# Main.net
KiCad netlist of a schematic drawn in Altium Designer
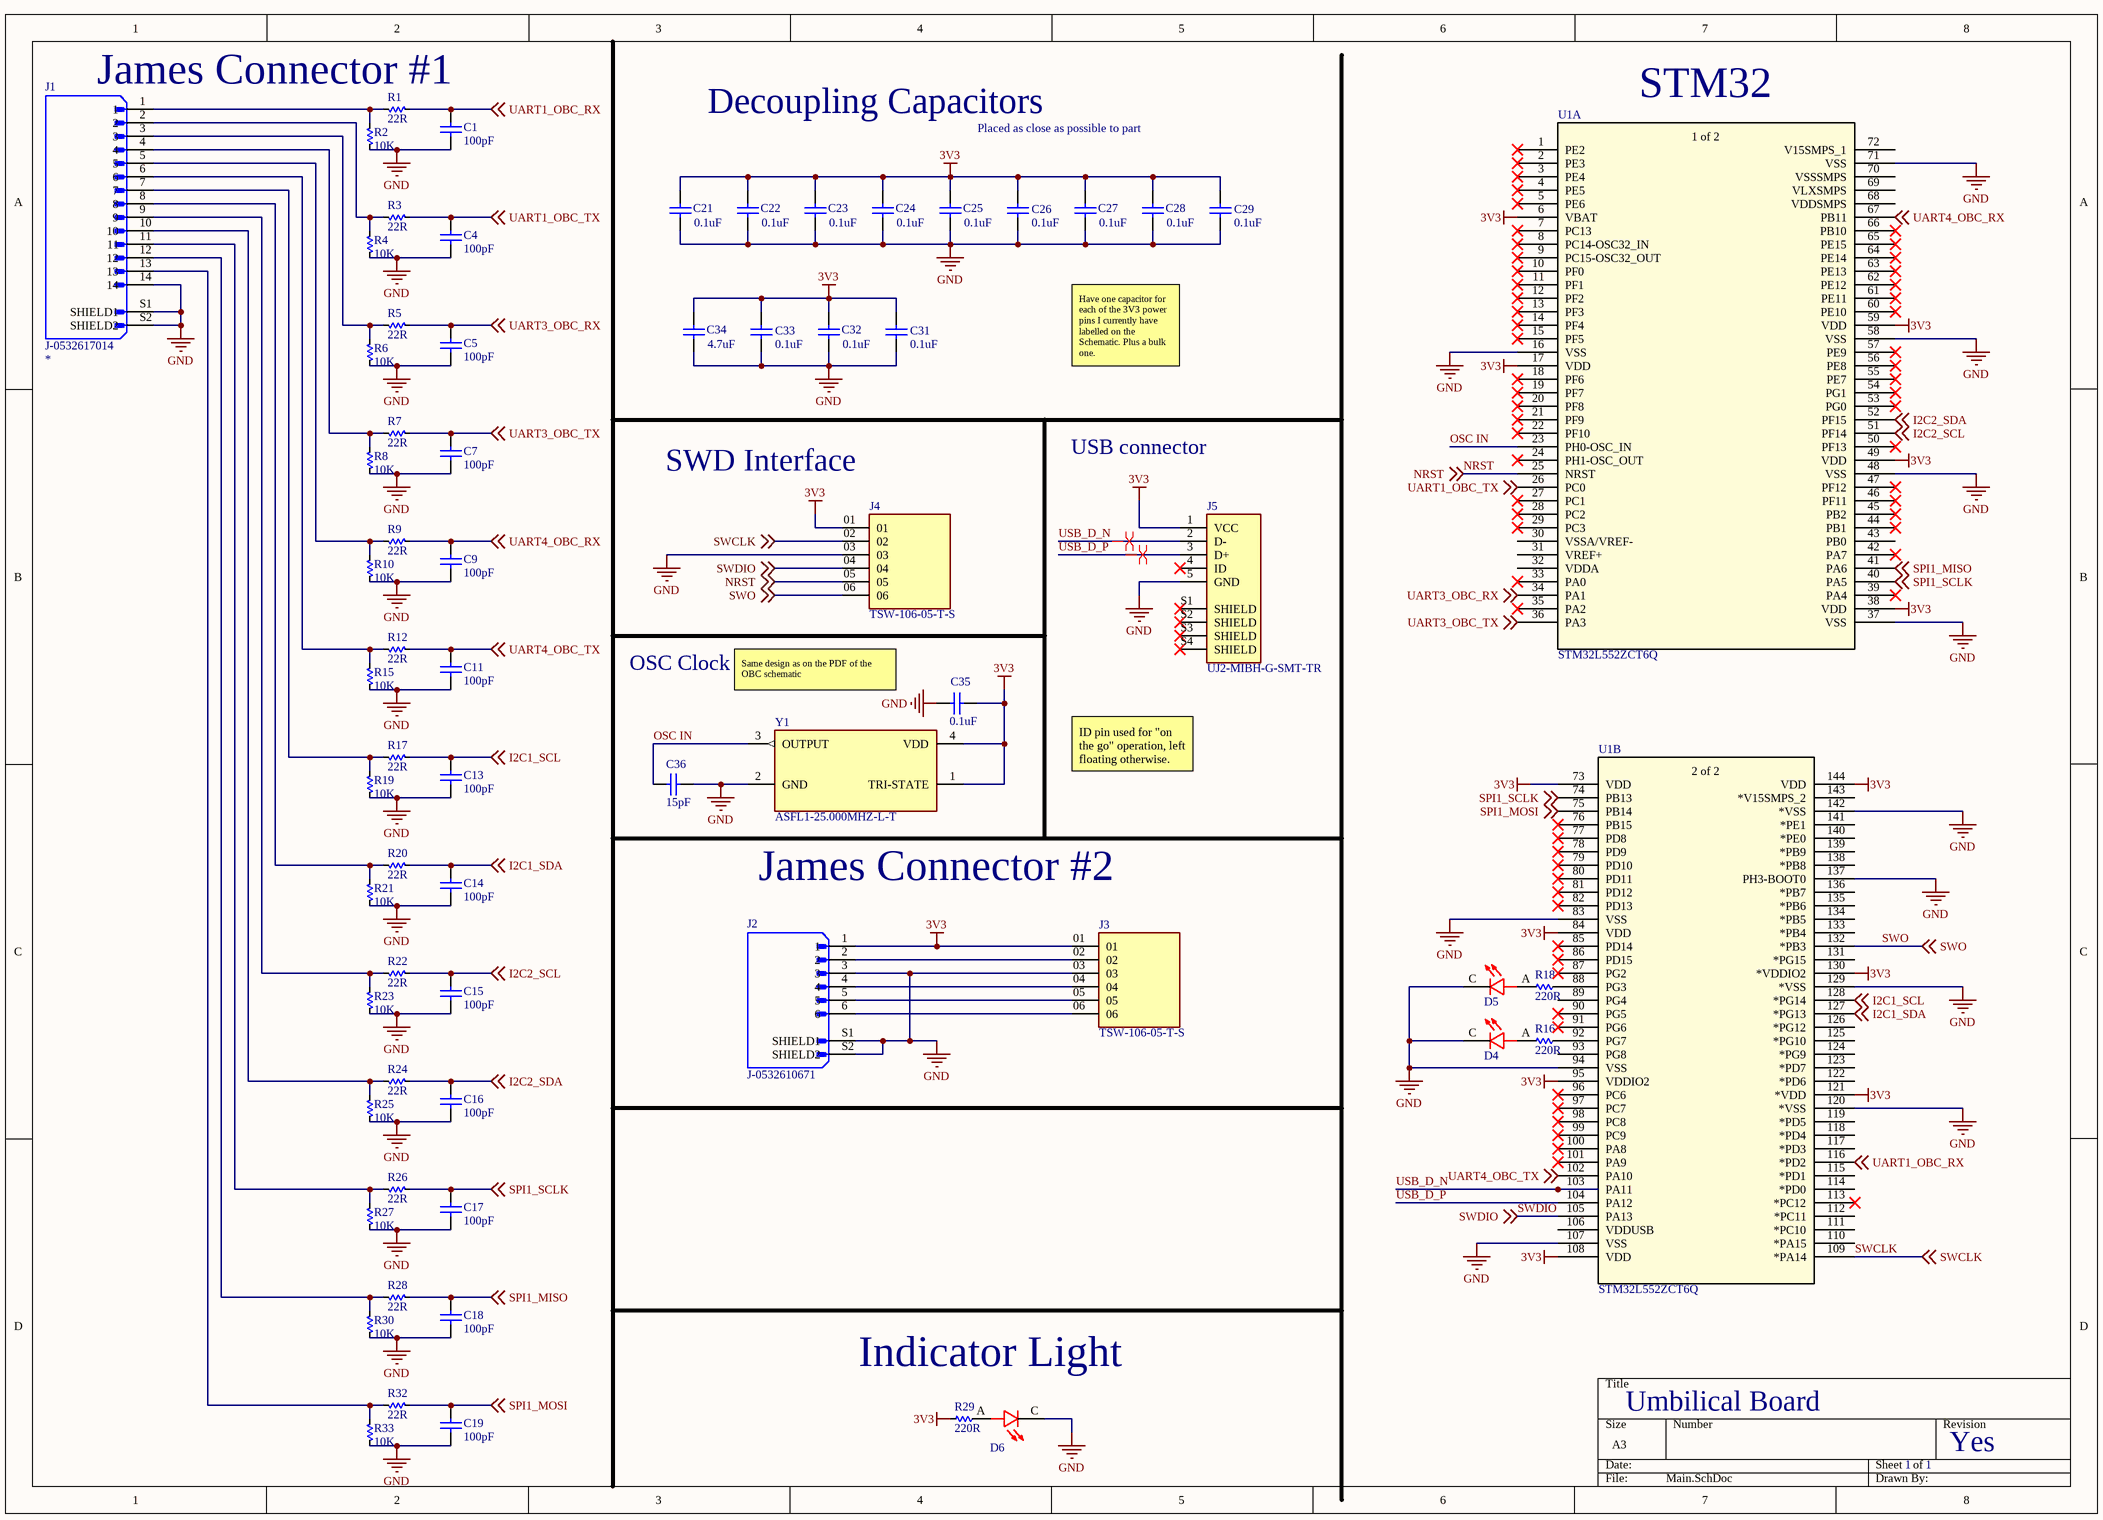
[diagram p0: Main.SchDoc]

(export (version "E")
  (design (tool "Eeschema 10.0.6"))
  (components
    (comp (ref "C1")
      (value "100pF")
      (footprint "CAPC1608X95X40NL15T15")
      (fields (field (name "PART NUMBER") "VJ0603A101FXACW1BC") (field (name "MANUFACTURER") "Vitramon"))
      (libsource (lib "Altium Content Vault") (part "CAP"))
    )
    (comp (ref "C4")
      (value "100pF")
      (footprint "CAPC1608X95X40NL15T15")
      (fields (field (name "PART NUMBER") "VJ0603A101FXACW1BC") (field (name "MANUFACTURER") "Vitramon"))
      (libsource (lib "Altium Content Vault") (part "CAP"))
    )
    (comp (ref "C5")
      (value "100pF")
      (footprint "CAPC1608X95X40NL15T15")
      (fields (field (name "PART NUMBER") "VJ0603A101FXACW1BC") (field (name "MANUFACTURER") "Vitramon"))
      (libsource (lib "Altium Content Vault") (part "CAP"))
    )
    (comp (ref "C7")
      (value "100pF")
      (footprint "CAPC1608X95X40NL15T15")
      (fields (field (name "PART NUMBER") "VJ0603A101FXACW1BC") (field (name "MANUFACTURER") "Vitramon"))
      (libsource (lib "Altium Content Vault") (part "CAP"))
    )
    (comp (ref "C9")
      (value "100pF")
      (footprint "CAPC1608X95X40NL15T15")
      (fields (field (name "PART NUMBER") "VJ0603A101FXACW1BC") (field (name "MANUFACTURER") "Vitramon"))
      (libsource (lib "Altium Content Vault") (part "CAP"))
    )
    (comp (ref "C11")
      (value "100pF")
      (footprint "CAPC1608X95X40NL15T15")
      (fields (field (name "PART NUMBER") "VJ0603A101FXACW1BC") (field (name "MANUFACTURER") "Vitramon"))
      (libsource (lib "Altium Content Vault") (part "CAP"))
    )
    (comp (ref "C13")
      (value "100pF")
      (footprint "CAPC1608X95X40NL15T15")
      (fields (field (name "PART NUMBER") "VJ0603A101FXACW1BC") (field (name "MANUFACTURER") "Vitramon"))
      (libsource (lib "Altium Content Vault") (part "CAP"))
    )
    (comp (ref "C14")
      (value "100pF")
      (footprint "CAPC1608X95X40NL15T15")
      (fields (field (name "PART NUMBER") "VJ0603A101FXACW1BC") (field (name "MANUFACTURER") "Vitramon"))
      (libsource (lib "Altium Content Vault") (part "CAP"))
    )
    (comp (ref "C15")
      (value "100pF")
      (footprint "CAPC1608X95X40NL15T15")
      (fields (field (name "PART NUMBER") "VJ0603A101FXACW1BC") (field (name "MANUFACTURER") "Vitramon"))
      (libsource (lib "Altium Content Vault") (part "CAP"))
    )
    (comp (ref "C16")
      (value "100pF")
      (footprint "CAPC1608X95X40NL15T15")
      (fields (field (name "PART NUMBER") "VJ0603A101FXACW1BC") (field (name "MANUFACTURER") "Vitramon"))
      (libsource (lib "Altium Content Vault") (part "CAP"))
    )
    (comp (ref "C17")
      (value "100pF")
      (footprint "CAPC1608X95X40NL15T15")
      (fields (field (name "PART NUMBER") "VJ0603A101FXACW1BC") (field (name "MANUFACTURER") "Vitramon"))
      (libsource (lib "Altium Content Vault") (part "CAP"))
    )
    (comp (ref "C18")
      (value "100pF")
      (footprint "CAPC1608X95X40NL15T15")
      (fields (field (name "PART NUMBER") "VJ0603A101FXACW1BC") (field (name "MANUFACTURER") "Vitramon"))
      (libsource (lib "Altium Content Vault") (part "CAP"))
    )
    (comp (ref "C19")
      (value "100pF")
      (footprint "CAPC1608X95X40NL15T15")
      (fields (field (name "PART NUMBER") "VJ0603A101FXACW1BC") (field (name "MANUFACTURER") "Vitramon"))
      (libsource (lib "Altium Content Vault") (part "CAP"))
    )
    (comp (ref "C21")
      (value "0.1uF")
      (footprint "CAPC1608X95X40NL15T15")
      (fields (field (name "PART NUMBER") "VJ0603A101FXACW1BC") (field (name "MANUFACTURER") "Vitramon"))
      (libsource (lib "Altium Content Vault") (part "CAP"))
    )
    (comp (ref "C22")
      (value "0.1uF")
      (footprint "CAPC1608X95X40NL15T15")
      (fields (field (name "PART NUMBER") "VJ0603A101FXACW1BC") (field (name "MANUFACTURER") "Vitramon"))
      (libsource (lib "Altium Content Vault") (part "CAP"))
    )
    (comp (ref "C23")
      (value "0.1uF")
      (footprint "CAPC1608X95X40NL15T15")
      (fields (field (name "PART NUMBER") "VJ0603A101FXACW1BC") (field (name "MANUFACTURER") "Vitramon"))
      (libsource (lib "Altium Content Vault") (part "CAP"))
    )
    (comp (ref "C24")
      (value "0.1uF")
      (footprint "CAPC1608X95X40NL15T15")
      (fields (field (name "PART NUMBER") "VJ0603A101FXACW1BC") (field (name "MANUFACTURER") "Vitramon"))
      (libsource (lib "Altium Content Vault") (part "CAP"))
    )
    (comp (ref "C25")
      (value "0.1uF")
      (footprint "CAPC1608X95X40NL15T15")
      (fields (field (name "PART NUMBER") "VJ0603A101FXACW1BC") (field (name "MANUFACTURER") "Vitramon"))
      (libsource (lib "Altium Content Vault") (part "CAP"))
    )
    (comp (ref "C26")
      (value "0.1uF")
      (footprint "CAPC1608X95X40NL15T15")
      (fields (field (name "PART NUMBER") "VJ0603A101FXACW1BC") (field (name "MANUFACTURER") "Vitramon"))
      (libsource (lib "Altium Content Vault") (part "CAP"))
    )
    (comp (ref "C27")
      (value "0.1uF")
      (footprint "CAPC1608X95X40NL15T15")
      (fields (field (name "PART NUMBER") "VJ0603A101FXACW1BC") (field (name "MANUFACTURER") "Vitramon"))
      (libsource (lib "Altium Content Vault") (part "CAP"))
    )
    (comp (ref "C28")
      (value "0.1uF")
      (footprint "CAPC1608X95X40NL15T15")
      (fields (field (name "PART NUMBER") "VJ0603A101FXACW1BC") (field (name "MANUFACTURER") "Vitramon"))
      (libsource (lib "Altium Content Vault") (part "CAP"))
    )
    (comp (ref "C29")
      (value "0.1uF")
      (footprint "CAPC1608X95X40NL15T15")
      (fields (field (name "PART NUMBER") "VJ0603A101FXACW1BC") (field (name "MANUFACTURER") "Vitramon"))
      (libsource (lib "Altium Content Vault") (part "CAP"))
    )
    (comp (ref "C31")
      (value "0.1uF")
      (footprint "CAPC1608X95X40NL15T15")
      (fields (field (name "PART NUMBER") "VJ0603A101FXACW1BC") (field (name "MANUFACTURER") "Vitramon"))
      (libsource (lib "Altium Content Vault") (part "CAP"))
    )
    (comp (ref "C32")
      (value "0.1uF")
      (footprint "CAPC1608X95X40NL15T15")
      (fields (field (name "PART NUMBER") "VJ0603A101FXACW1BC") (field (name "MANUFACTURER") "Vitramon"))
      (libsource (lib "Altium Content Vault") (part "CAP"))
    )
    (comp (ref "C33")
      (value "0.1uF")
      (footprint "CAPC1608X95X40NL15T15")
      (fields (field (name "PART NUMBER") "VJ0603A101FXACW1BC") (field (name "MANUFACTURER") "Vitramon"))
      (libsource (lib "Altium Content Vault") (part "CAP"))
    )
    (comp (ref "C34")
      (value "4.7uF")
      (footprint "CAPC1608X95X40NL15T15")
      (fields (field (name "PART NUMBER") "VJ0603A101FXACW1BC") (field (name "MANUFACTURER") "Vitramon"))
      (libsource (lib "Altium Content Vault") (part "CAP"))
    )
    (comp (ref "C35")
      (value "0.1uF")
      (footprint "CAPC1608X95X40NL15T15")
      (fields (field (name "PART NUMBER") "VJ0603A101FXACW1BC") (field (name "MANUFACTURER") "Vitramon"))
      (libsource (lib "Altium Content Vault") (part "CAP"))
    )
    (comp (ref "C36")
      (value "15pF")
      (footprint "CAPC1608X95X40NL15T15")
      (fields (field (name "PART NUMBER") "VJ0603A101FXACW1BC") (field (name "MANUFACTURER") "Vitramon"))
      (libsource (lib "Altium Content Vault") (part "CAP"))
    )
    (comp (ref "D4")
      (value "D-SML-D12U1WT86")
      (footprint "D-SML-D12U1WT86")
      (description "Red 620nm LED Indication - Discrete 2.2V 0603 _1608 Metric")
      (fields
        (field (name "MANUFACTURER PART #") "SML-D12U1WT86")
        (field (name "MANUFACTURER") "Rohm Semiconductor")
      )
      (libsource (lib "OBC Development Board") (part "D-SML-D12U1WT86"))
    )
    (comp (ref "D5")
      (value "D-SML-D12U1WT86")
      (footprint "D-SML-D12U1WT86")
      (description "Red 620nm LED Indication - Discrete 2.2V 0603 _1608 Metric")
      (fields
        (field (name "MANUFACTURER PART #") "SML-D12U1WT86")
        (field (name "MANUFACTURER") "Rohm Semiconductor")
      )
      (libsource (lib "OBC Development Board") (part "D-SML-D12U1WT86"))
    )
    (comp (ref "D6")
      (value "D-SML-D12U1WT86")
      (footprint "D-SML-D12U1WT86")
      (description "Red 620nm LED Indication - Discrete 2.2V 0603 _1608 Metric")
      (fields
        (field (name "MANUFACTURER PART #") "SML-D12U1WT86")
        (field (name "MANUFACTURER") "Rohm Semiconductor")
      )
      (libsource (lib "OBC Development Board") (part "D-SML-D12U1WT86"))
    )
    (comp (ref "J1")
      (value "J-0532617014")
      (footprint "J-532617014")
      (description "Connector Header Surface Mount, Right Angle 14 position 0.049 (1.25mm)")
      (fields
        (field (name "MANUFACTURER") "Molex")
        (field (name "MANUFACTURER PART #") "0532617014")
        (field (name "2") "*")
      )
      (libsource (lib "UmbilicalBoard") (part "J-0532617014"))
    )
    (comp (ref "J2")
      (value "J-0532610671")
      (footprint "J-0532610671")
      (description "CONN HEADER SMD R/A 6POS 1.25MM")
      (fields
        (field (name "MANFACTURER PART #") "0532610671")
        (field (name "DISTRIBUTOR PART #") "WM7624CT-ND")
      )
      (libsource (lib "UmbilicalBoard") (part "J-0532610671"))
    )
    (comp (ref "J3")
      (value "TSW-106-05-T-S")
      (footprint "TSW-106-05-T-S")
      (description "CONN HEADER VERT 6POS 2.54MM")
      (fields (field (name "MF") "Samtec"))
      (libsource (lib "UmbilicalBoard") (part "TSW-106-05-T-S"))
    )
    (comp (ref "J4")
      (value "TSW-106-05-T-S")
      (footprint "TSW-106-05-T-S")
      (description "CONN HEADER VERT 6POS 2.54MM")
      (fields (field (name "MF") "Samtec"))
      (libsource (lib "UmbilicalBoard") (part "TSW-106-05-T-S"))
    )
    (comp (ref "J5")
      (value "UJ2-MIBH-G-SMT-TR")
      (footprint "UJ2-MIBH-G-SMT-TR")
      (description "USB JACK, 2.0, MICRO B TYPE, 5 P")
      (fields (field (name "MF") "CUI Devices"))
      (libsource (lib "UmbilicalBoard") (part "UJ2-MIBH-G-SMT-TR"))
    )
    (comp (ref "R1")
      (value "22R")
      (footprint "0603")
      (description "22 Ohms ±0.5% 0.063W, 1/16W Chip Resistor 0603 (1608 Metric) - Thin Film")
      (fields (field (name "DISTRIBUTOR PART #") "RR08Q22DCT-ND") (field (name "MANUFACTURER") "Susumu"))
      (libsource (lib "UmbilicalBoard") (part "RT-22R0-F-1/16W-0603"))
    )
    (comp (ref "R2")
      (value "10K")
      (footprint "0603")
      (description "10 kOhms ±0.1% 0.063W, 1/16W Chip Resistor 0603 (1608 Metric) - Thin Film")
      (fields
        (field (name "DISTRIBUTOR PART #") "A119886CT-ND")
        (field (name "MANUFACTURER") "TE Connectivity Passive Product")
      )
      (libsource (lib "UmbilicalBoard") (part "RT-10K0-F-1/16W-0603"))
    )
    (comp (ref "R3")
      (value "22R")
      (footprint "0603")
      (description "22 Ohms ±0.5% 0.063W, 1/16W Chip Resistor 0603 (1608 Metric) - Thin Film")
      (fields (field (name "DISTRIBUTOR PART #") "RR08Q22DCT-ND") (field (name "MANUFACTURER") "Susumu"))
      (libsource (lib "UmbilicalBoard") (part "RT-22R0-F-1/16W-0603"))
    )
    (comp (ref "R4")
      (value "10K")
      (footprint "0603")
      (description "10 kOhms ±0.1% 0.063W, 1/16W Chip Resistor 0603 (1608 Metric) - Thin Film")
      (fields
        (field (name "DISTRIBUTOR PART #") "A119886CT-ND")
        (field (name "MANUFACTURER") "TE Connectivity Passive Product")
      )
      (libsource (lib "UmbilicalBoard") (part "RT-10K0-F-1/16W-0603"))
    )
    (comp (ref "R5")
      (value "22R")
      (footprint "0603")
      (description "22 Ohms ±0.5% 0.063W, 1/16W Chip Resistor 0603 (1608 Metric) - Thin Film")
      (fields (field (name "DISTRIBUTOR PART #") "RR08Q22DCT-ND") (field (name "MANUFACTURER") "Susumu"))
      (libsource (lib "UmbilicalBoard") (part "RT-22R0-F-1/16W-0603"))
    )
    (comp (ref "R6")
      (value "10K")
      (footprint "0603")
      (description "10 kOhms ±0.1% 0.063W, 1/16W Chip Resistor 0603 (1608 Metric) - Thin Film")
      (fields
        (field (name "DISTRIBUTOR PART #") "A119886CT-ND")
        (field (name "MANUFACTURER") "TE Connectivity Passive Product")
      )
      (libsource (lib "UmbilicalBoard") (part "RT-10K0-F-1/16W-0603"))
    )
    (comp (ref "R7")
      (value "22R")
      (footprint "0603")
      (description "22 Ohms ±0.5% 0.063W, 1/16W Chip Resistor 0603 (1608 Metric) - Thin Film")
      (fields (field (name "DISTRIBUTOR PART #") "RR08Q22DCT-ND") (field (name "MANUFACTURER") "Susumu"))
      (libsource (lib "UmbilicalBoard") (part "RT-22R0-F-1/16W-0603"))
    )
    (comp (ref "R8")
      (value "10K")
      (footprint "0603")
      (description "10 kOhms ±0.1% 0.063W, 1/16W Chip Resistor 0603 (1608 Metric) - Thin Film")
      (fields
        (field (name "DISTRIBUTOR PART #") "A119886CT-ND")
        (field (name "MANUFACTURER") "TE Connectivity Passive Product")
      )
      (libsource (lib "UmbilicalBoard") (part "RT-10K0-F-1/16W-0603"))
    )
    (comp (ref "R9")
      (value "22R")
      (footprint "0603")
      (description "22 Ohms ±0.5% 0.063W, 1/16W Chip Resistor 0603 (1608 Metric) - Thin Film")
      (fields (field (name "DISTRIBUTOR PART #") "RR08Q22DCT-ND") (field (name "MANUFACTURER") "Susumu"))
      (libsource (lib "UmbilicalBoard") (part "RT-22R0-F-1/16W-0603"))
    )
    (comp (ref "R10")
      (value "10K")
      (footprint "0603")
      (description "10 kOhms ±0.1% 0.063W, 1/16W Chip Resistor 0603 (1608 Metric) - Thin Film")
      (fields
        (field (name "DISTRIBUTOR PART #") "A119886CT-ND")
        (field (name "MANUFACTURER") "TE Connectivity Passive Product")
      )
      (libsource (lib "UmbilicalBoard") (part "RT-10K0-F-1/16W-0603"))
    )
    (comp (ref "R12")
      (value "22R")
      (footprint "0603")
      (description "22 Ohms ±0.5% 0.063W, 1/16W Chip Resistor 0603 (1608 Metric) - Thin Film")
      (fields (field (name "DISTRIBUTOR PART #") "RR08Q22DCT-ND") (field (name "MANUFACTURER") "Susumu"))
      (libsource (lib "UmbilicalBoard") (part "RT-22R0-F-1/16W-0603"))
    )
    (comp (ref "R15")
      (value "10K")
      (footprint "0603")
      (description "10 kOhms ±0.1% 0.063W, 1/16W Chip Resistor 0603 (1608 Metric) - Thin Film")
      (fields
        (field (name "DISTRIBUTOR PART #") "A119886CT-ND")
        (field (name "MANUFACTURER") "TE Connectivity Passive Product")
      )
      (libsource (lib "UmbilicalBoard") (part "RT-10K0-F-1/16W-0603"))
    )
    (comp (ref "R16")
      (value "220R")
      (footprint "0603")
      (description "220 Ohms ±0.5% 0.063W, 1/16W Chip Resistor 0603 (1608 Metric) - Thin Film")
      (fields (field (name "DISTRIBUTOR PART #") "RR08P220DCT-ND") (field (name "MANUFACTURER") "Susumu"))
      (libsource (lib "OBC Development Board") (part "RT-220R-F-1/16W-0603"))
    )
    (comp (ref "R17")
      (value "22R")
      (footprint "0603")
      (description "22 Ohms ±0.5% 0.063W, 1/16W Chip Resistor 0603 (1608 Metric) - Thin Film")
      (fields (field (name "DISTRIBUTOR PART #") "RR08Q22DCT-ND") (field (name "MANUFACTURER") "Susumu"))
      (libsource (lib "UmbilicalBoard") (part "RT-22R0-F-1/16W-0603"))
    )
    (comp (ref "R18")
      (value "220R")
      (footprint "0603")
      (description "220 Ohms ±0.5% 0.063W, 1/16W Chip Resistor 0603 (1608 Metric) - Thin Film")
      (fields (field (name "DISTRIBUTOR PART #") "RR08P220DCT-ND") (field (name "MANUFACTURER") "Susumu"))
      (libsource (lib "OBC Development Board") (part "RT-220R-F-1/16W-0603"))
    )
    (comp (ref "R19")
      (value "10K")
      (footprint "0603")
      (description "10 kOhms ±0.1% 0.063W, 1/16W Chip Resistor 0603 (1608 Metric) - Thin Film")
      (fields
        (field (name "DISTRIBUTOR PART #") "A119886CT-ND")
        (field (name "MANUFACTURER") "TE Connectivity Passive Product")
      )
      (libsource (lib "UmbilicalBoard") (part "RT-10K0-F-1/16W-0603"))
    )
    (comp (ref "R20")
      (value "22R")
      (footprint "0603")
      (description "22 Ohms ±0.5% 0.063W, 1/16W Chip Resistor 0603 (1608 Metric) - Thin Film")
      (fields (field (name "DISTRIBUTOR PART #") "RR08Q22DCT-ND") (field (name "MANUFACTURER") "Susumu"))
      (libsource (lib "UmbilicalBoard") (part "RT-22R0-F-1/16W-0603"))
    )
    (comp (ref "R21")
      (value "10K")
      (footprint "0603")
      (description "10 kOhms ±0.1% 0.063W, 1/16W Chip Resistor 0603 (1608 Metric) - Thin Film")
      (fields
        (field (name "DISTRIBUTOR PART #") "A119886CT-ND")
        (field (name "MANUFACTURER") "TE Connectivity Passive Product")
      )
      (libsource (lib "UmbilicalBoard") (part "RT-10K0-F-1/16W-0603"))
    )
    (comp (ref "R22")
      (value "22R")
      (footprint "0603")
      (description "22 Ohms ±0.5% 0.063W, 1/16W Chip Resistor 0603 (1608 Metric) - Thin Film")
      (fields (field (name "DISTRIBUTOR PART #") "RR08Q22DCT-ND") (field (name "MANUFACTURER") "Susumu"))
      (libsource (lib "UmbilicalBoard") (part "RT-22R0-F-1/16W-0603"))
    )
    (comp (ref "R23")
      (value "10K")
      (footprint "0603")
      (description "10 kOhms ±0.1% 0.063W, 1/16W Chip Resistor 0603 (1608 Metric) - Thin Film")
      (fields
        (field (name "DISTRIBUTOR PART #") "A119886CT-ND")
        (field (name "MANUFACTURER") "TE Connectivity Passive Product")
      )
      (libsource (lib "UmbilicalBoard") (part "RT-10K0-F-1/16W-0603"))
    )
    (comp (ref "R24")
      (value "22R")
      (footprint "0603")
      (description "22 Ohms ±0.5% 0.063W, 1/16W Chip Resistor 0603 (1608 Metric) - Thin Film")
      (fields (field (name "DISTRIBUTOR PART #") "RR08Q22DCT-ND") (field (name "MANUFACTURER") "Susumu"))
      (libsource (lib "UmbilicalBoard") (part "RT-22R0-F-1/16W-0603"))
    )
    (comp (ref "R25")
      (value "10K")
      (footprint "0603")
      (description "10 kOhms ±0.1% 0.063W, 1/16W Chip Resistor 0603 (1608 Metric) - Thin Film")
      (fields
        (field (name "DISTRIBUTOR PART #") "A119886CT-ND")
        (field (name "MANUFACTURER") "TE Connectivity Passive Product")
      )
      (libsource (lib "UmbilicalBoard") (part "RT-10K0-F-1/16W-0603"))
    )
    (comp (ref "R26")
      (value "22R")
      (footprint "0603")
      (description "22 Ohms ±0.5% 0.063W, 1/16W Chip Resistor 0603 (1608 Metric) - Thin Film")
      (fields (field (name "DISTRIBUTOR PART #") "RR08Q22DCT-ND") (field (name "MANUFACTURER") "Susumu"))
      (libsource (lib "UmbilicalBoard") (part "RT-22R0-F-1/16W-0603"))
    )
    (comp (ref "R27")
      (value "10K")
      (footprint "0603")
      (description "10 kOhms ±0.1% 0.063W, 1/16W Chip Resistor 0603 (1608 Metric) - Thin Film")
      (fields
        (field (name "DISTRIBUTOR PART #") "A119886CT-ND")
        (field (name "MANUFACTURER") "TE Connectivity Passive Product")
      )
      (libsource (lib "UmbilicalBoard") (part "RT-10K0-F-1/16W-0603"))
    )
    (comp (ref "R28")
      (value "22R")
      (footprint "0603")
      (description "22 Ohms ±0.5% 0.063W, 1/16W Chip Resistor 0603 (1608 Metric) - Thin Film")
      (fields (field (name "DISTRIBUTOR PART #") "RR08Q22DCT-ND") (field (name "MANUFACTURER") "Susumu"))
      (libsource (lib "UmbilicalBoard") (part "RT-22R0-F-1/16W-0603"))
    )
    (comp (ref "R29")
      (value "220R")
      (footprint "0603")
      (description "220 Ohms ±0.5% 0.063W, 1/16W Chip Resistor 0603 (1608 Metric) - Thin Film")
      (fields (field (name "DISTRIBUTOR PART #") "RR08P220DCT-ND") (field (name "MANUFACTURER") "Susumu"))
      (libsource (lib "OBC Development Board") (part "RT-220R-F-1/16W-0603"))
    )
    (comp (ref "R30")
      (value "10K")
      (footprint "0603")
      (description "10 kOhms ±0.1% 0.063W, 1/16W Chip Resistor 0603 (1608 Metric) - Thin Film")
      (fields
        (field (name "DISTRIBUTOR PART #") "A119886CT-ND")
        (field (name "MANUFACTURER") "TE Connectivity Passive Product")
      )
      (libsource (lib "UmbilicalBoard") (part "RT-10K0-F-1/16W-0603"))
    )
    (comp (ref "R32")
      (value "22R")
      (footprint "0603")
      (description "22 Ohms ±0.5% 0.063W, 1/16W Chip Resistor 0603 (1608 Metric) - Thin Film")
      (fields (field (name "DISTRIBUTOR PART #") "RR08Q22DCT-ND") (field (name "MANUFACTURER") "Susumu"))
      (libsource (lib "UmbilicalBoard") (part "RT-22R0-F-1/16W-0603"))
    )
    (comp (ref "R33")
      (value "10K")
      (footprint "0603")
      (description "10 kOhms ±0.1% 0.063W, 1/16W Chip Resistor 0603 (1608 Metric) - Thin Film")
      (fields
        (field (name "DISTRIBUTOR PART #") "A119886CT-ND")
        (field (name "MANUFACTURER") "TE Connectivity Passive Product")
      )
      (libsource (lib "UmbilicalBoard") (part "RT-10K0-F-1/16W-0603"))
    )
    (comp (ref "U1")
      (value "STM32L552ZCT6Q")
      (footprint "STM32L552ZCT6Q")
      (description "IC MCU 32BIT 256KB FLASH 144LQFP")
      (fields (field (name "COPYRIGHT") "Copyright (C) 2023 Ultra Librarian. All rights reserved."))
      (libsource (lib "UmbilicalBoard") (part "STM32L552ZCT6Q"))
    )
    (comp (ref "Y1")
      (value "ASFL1-25.000MHZ-L-T")
      (footprint "XTAL_ASFL1-25.000MHZ-L-T")
      (description "XTAL OSC XO 25.0000MHZ HCMOS TTL")
      (libsource (lib "UmbilicalBoard") (part "ASFL1-25.000MHZ-L-T"))
    )
  )
  (nets
    (net (code "1") (name "/OSC IN") (class "Default")
      (node (ref "C36") (pin "2") (pinfunction "2_2") (pintype "passive"))
      (node (ref "U1") (pin "23") (pinfunction "PH0-OSC_IN_23") (pintype "open_collector"))
      (node (ref "Y1") (pin "3") (pinfunction "OUTPUT_3") (pintype "output"))
    )
    (net (code "2") (name "/USB_D_N") (class "Default")
      (node (ref "J5") (pin "2") (pinfunction "D-_2") (pintype "passive"))
      (node (ref "U1") (pin "103") (pinfunction "PA11_103") (pintype "passive"))
    )
    (net (code "3") (name "/USB_D_P") (class "Default")
      (node (ref "J5") (pin "3") (pinfunction "D+_3") (pintype "passive"))
      (node (ref "U1") (pin "104") (pinfunction "PA12_104") (pintype "passive"))
    )
    (net (code "4") (name "3V3") (class "Default")
      (node (ref "C21") (pin "2") (pinfunction "2_2") (pintype "passive"))
      (node (ref "C22") (pin "2") (pinfunction "2_2") (pintype "passive"))
      (node (ref "C23") (pin "2") (pinfunction "2_2") (pintype "passive"))
      (node (ref "C24") (pin "2") (pinfunction "2_2") (pintype "passive"))
      (node (ref "C25") (pin "2") (pinfunction "2_2") (pintype "passive"))
      (node (ref "C26") (pin "2") (pinfunction "2_2") (pintype "passive"))
      (node (ref "C27") (pin "2") (pinfunction "2_2") (pintype "passive"))
      (node (ref "C28") (pin "2") (pinfunction "2_2") (pintype "passive"))
      (node (ref "C29") (pin "2") (pinfunction "2_2") (pintype "passive"))
      (node (ref "C31") (pin "2") (pinfunction "2_2") (pintype "passive"))
      (node (ref "C32") (pin "2") (pinfunction "2_2") (pintype "passive"))
      (node (ref "C33") (pin "2") (pinfunction "2_2") (pintype "passive"))
      (node (ref "C34") (pin "2") (pinfunction "2_2") (pintype "passive"))
      (node (ref "C35") (pin "1") (pinfunction "1_1") (pintype "passive"))
      (node (ref "J2") (pin "1") (pinfunction "1_1") (pintype "passive"))
      (node (ref "J3") (pin "01") (pinfunction "01_01") (pintype "passive"))
      (node (ref "J4") (pin "01") (pinfunction "01_01") (pintype "passive"))
      (node (ref "J5") (pin "1") (pinfunction "VCC_1") (pintype "power_in"))
      (node (ref "R29") (pin "2") (pintype "passive"))
      (node (ref "U1") (pin "108") (pinfunction "VDD_108") (pintype "passive"))
      (node (ref "U1") (pin "121") (pinfunction "*VDD_121") (pintype "passive"))
      (node (ref "U1") (pin "130") (pinfunction "*VDDIO2_130") (pintype "passive"))
      (node (ref "U1") (pin "144") (pinfunction "VDD_144") (pintype "passive"))
      (node (ref "U1") (pin "17") (pinfunction "VDD_17") (pintype "power_in"))
      (node (ref "U1") (pin "38") (pinfunction "VDD_38") (pintype "power_in"))
      (node (ref "U1") (pin "49") (pinfunction "VDD_49") (pintype "power_in"))
      (node (ref "U1") (pin "59") (pinfunction "VDD_59") (pintype "power_in"))
      (node (ref "U1") (pin "6") (pinfunction "VBAT_6") (pintype "power_in"))
      (node (ref "U1") (pin "73") (pinfunction "VDD_73") (pintype "passive"))
      (node (ref "U1") (pin "84") (pinfunction "VDD_84") (pintype "passive"))
      (node (ref "U1") (pin "95") (pinfunction "VDDIO2_95") (pintype "passive"))
      (node (ref "Y1") (pin "1") (pinfunction "TRI-STATE_1") (pintype "passive"))
      (node (ref "Y1") (pin "4") (pinfunction "VDD_4") (pintype "power_in"))
    )
    (net (code "5") (name "GND") (class "Default")
      (node (ref "C1") (pin "1") (pinfunction "1_1") (pintype "passive"))
      (node (ref "C11") (pin "1") (pinfunction "1_1") (pintype "passive"))
      (node (ref "C13") (pin "1") (pinfunction "1_1") (pintype "passive"))
      (node (ref "C14") (pin "1") (pinfunction "1_1") (pintype "passive"))
      (node (ref "C15") (pin "1") (pinfunction "1_1") (pintype "passive"))
      (node (ref "C16") (pin "1") (pinfunction "1_1") (pintype "passive"))
      (node (ref "C17") (pin "1") (pinfunction "1_1") (pintype "passive"))
      (node (ref "C18") (pin "1") (pinfunction "1_1") (pintype "passive"))
      (node (ref "C19") (pin "1") (pinfunction "1_1") (pintype "passive"))
      (node (ref "C21") (pin "1") (pinfunction "1_1") (pintype "passive"))
      (node (ref "C22") (pin "1") (pinfunction "1_1") (pintype "passive"))
      (node (ref "C23") (pin "1") (pinfunction "1_1") (pintype "passive"))
      (node (ref "C24") (pin "1") (pinfunction "1_1") (pintype "passive"))
      (node (ref "C25") (pin "1") (pinfunction "1_1") (pintype "passive"))
      (node (ref "C26") (pin "1") (pinfunction "1_1") (pintype "passive"))
      (node (ref "C27") (pin "1") (pinfunction "1_1") (pintype "passive"))
      (node (ref "C28") (pin "1") (pinfunction "1_1") (pintype "passive"))
      (node (ref "C29") (pin "1") (pinfunction "1_1") (pintype "passive"))
      (node (ref "C31") (pin "1") (pinfunction "1_1") (pintype "passive"))
      (node (ref "C32") (pin "1") (pinfunction "1_1") (pintype "passive"))
      (node (ref "C33") (pin "1") (pinfunction "1_1") (pintype "passive"))
      (node (ref "C34") (pin "1") (pinfunction "1_1") (pintype "passive"))
      (node (ref "C35") (pin "2") (pinfunction "2_2") (pintype "passive"))
      (node (ref "C36") (pin "1") (pinfunction "1_1") (pintype "passive"))
      (node (ref "C4") (pin "1") (pinfunction "1_1") (pintype "passive"))
      (node (ref "C5") (pin "1") (pinfunction "1_1") (pintype "passive"))
      (node (ref "C7") (pin "1") (pinfunction "1_1") (pintype "passive"))
      (node (ref "C9") (pin "1") (pinfunction "1_1") (pintype "passive"))
      (node (ref "D4") (pin "C") (pinfunction "C_C") (pintype "passive"))
      (node (ref "D5") (pin "C") (pinfunction "C_C") (pintype "passive"))
      (node (ref "D6") (pin "C") (pinfunction "C_C") (pintype "passive"))
      (node (ref "J1") (pin "14") (pinfunction "14_14") (pintype "passive"))
      (node (ref "J1") (pin "S1") (pinfunction "SHIELD1_S1") (pintype "passive"))
      (node (ref "J1") (pin "S2") (pinfunction "SHIELD2_S2") (pintype "passive"))
      (node (ref "J2") (pin "3") (pinfunction "3_3") (pintype "passive"))
      (node (ref "J2") (pin "S1") (pinfunction "SHIELD1_S1") (pintype "passive"))
      (node (ref "J2") (pin "S2") (pinfunction "SHIELD2_S2") (pintype "passive"))
      (node (ref "J3") (pin "03") (pinfunction "03_03") (pintype "passive"))
      (node (ref "J4") (pin "03") (pinfunction "03_03") (pintype "passive"))
      (node (ref "J5") (pin "5") (pinfunction "GND_5") (pintype "power_in"))
      (node (ref "R10") (pin "1") (pintype "passive"))
      (node (ref "R15") (pin "1") (pintype "passive"))
      (node (ref "R19") (pin "1") (pintype "passive"))
      (node (ref "R2") (pin "1") (pintype "passive"))
      (node (ref "R21") (pin "1") (pintype "passive"))
      (node (ref "R23") (pin "1") (pintype "passive"))
      (node (ref "R25") (pin "1") (pintype "passive"))
      (node (ref "R27") (pin "1") (pintype "passive"))
      (node (ref "R30") (pin "1") (pintype "passive"))
      (node (ref "R33") (pin "1") (pintype "passive"))
      (node (ref "R4") (pin "1") (pintype "passive"))
      (node (ref "R6") (pin "1") (pintype "passive"))
      (node (ref "R8") (pin "1") (pintype "passive"))
      (node (ref "U1") (pin "107") (pinfunction "VSS_107") (pintype "passive"))
      (node (ref "U1") (pin "120") (pinfunction "*VSS_120") (pintype "passive"))
      (node (ref "U1") (pin "129") (pinfunction "*VSS_129") (pintype "passive"))
      (node (ref "U1") (pin "137") (pinfunction "PH3-BOOT0_137") (pintype "passive"))
      (node (ref "U1") (pin "142") (pinfunction "*VSS_142") (pintype "passive"))
      (node (ref "U1") (pin "16") (pinfunction "VSS_16") (pintype "passive"))
      (node (ref "U1") (pin "37") (pinfunction "VSS_37") (pintype "passive"))
      (node (ref "U1") (pin "48") (pinfunction "VSS_48") (pintype "passive"))
      (node (ref "U1") (pin "58") (pinfunction "VSS_58") (pintype "passive"))
      (node (ref "U1") (pin "71") (pinfunction "VSS_71") (pintype "passive"))
      (node (ref "U1") (pin "83") (pinfunction "VSS_83") (pintype "passive"))
      (node (ref "U1") (pin "94") (pinfunction "VSS_94") (pintype "passive"))
      (node (ref "Y1") (pin "2") (pinfunction "GND_2") (pintype "power_in"))
    )
    (net (code "6") (name "I2C1_SCL") (class "Default")
      (node (ref "C13") (pin "2") (pinfunction "2_2") (pintype "passive"))
      (node (ref "R17") (pin "2") (pintype "passive"))
      (node (ref "U1") (pin "128") (pinfunction "*PG14_128") (pintype "passive"))
    )
    (net (code "7") (name "I2C1_SDA") (class "Default")
      (node (ref "C14") (pin "2") (pinfunction "2_2") (pintype "passive"))
      (node (ref "R20") (pin "2") (pintype "passive"))
      (node (ref "U1") (pin "127") (pinfunction "*PG13_127") (pintype "passive"))
    )
    (net (code "8") (name "I2C2_SCL") (class "Default")
      (node (ref "C15") (pin "2") (pinfunction "2_2") (pintype "passive"))
      (node (ref "R22") (pin "2") (pintype "passive"))
      (node (ref "U1") (pin "51") (pinfunction "PF14_51") (pintype "passive"))
    )
    (net (code "9") (name "I2C2_SDA") (class "Default")
      (node (ref "C16") (pin "2") (pinfunction "2_2") (pintype "passive"))
      (node (ref "R24") (pin "2") (pintype "passive"))
      (node (ref "U1") (pin "52") (pinfunction "PF15_52") (pintype "passive"))
    )
    (net (code "10") (name "NRST") (class "Default")
      (node (ref "J4") (pin "05") (pinfunction "05_05") (pintype "passive"))
      (node (ref "U1") (pin "25") (pinfunction "NRST_25") (pintype "open_collector"))
    )
    (net (code "11") (name "Net-(D4-PadA)") (class "Default")
      (node (ref "D4") (pin "A") (pinfunction "A_A") (pintype "passive"))
      (node (ref "R16") (pin "1") (pintype "passive"))
    )
    (net (code "12") (name "Net-(D5-PadA)") (class "Default")
      (node (ref "D5") (pin "A") (pinfunction "A_A") (pintype "passive"))
      (node (ref "R18") (pin "1") (pintype "passive"))
    )
    (net (code "13") (name "Net-(D6-PadA)") (class "Default")
      (node (ref "D6") (pin "A") (pinfunction "A_A") (pintype "passive"))
      (node (ref "R29") (pin "1") (pintype "passive"))
    )
    (net (code "14") (name "Net-(J1-Pad1)") (class "Default")
      (node (ref "J1") (pin "1") (pinfunction "1_1") (pintype "passive"))
      (node (ref "R1") (pin "1") (pintype "passive"))
      (node (ref "R2") (pin "2") (pintype "passive"))
    )
    (net (code "15") (name "Net-(J1-Pad2)") (class "Default")
      (node (ref "J1") (pin "2") (pinfunction "2_2") (pintype "passive"))
      (node (ref "R3") (pin "1") (pintype "passive"))
      (node (ref "R4") (pin "2") (pintype "passive"))
    )
    (net (code "16") (name "Net-(J1-Pad3)") (class "Default")
      (node (ref "J1") (pin "3") (pinfunction "3_3") (pintype "passive"))
      (node (ref "R5") (pin "1") (pintype "passive"))
      (node (ref "R6") (pin "2") (pintype "passive"))
    )
    (net (code "17") (name "Net-(J1-Pad4)") (class "Default")
      (node (ref "J1") (pin "4") (pinfunction "4_4") (pintype "passive"))
      (node (ref "R7") (pin "1") (pintype "passive"))
      (node (ref "R8") (pin "2") (pintype "passive"))
    )
    (net (code "18") (name "Net-(J1-Pad5)") (class "Default")
      (node (ref "J1") (pin "5") (pinfunction "5_5") (pintype "passive"))
      (node (ref "R10") (pin "2") (pintype "passive"))
      (node (ref "R9") (pin "1") (pintype "passive"))
    )
    (net (code "19") (name "Net-(J1-Pad6)") (class "Default")
      (node (ref "J1") (pin "6") (pinfunction "6_6") (pintype "passive"))
      (node (ref "R12") (pin "1") (pintype "passive"))
      (node (ref "R15") (pin "2") (pintype "passive"))
    )
    (net (code "20") (name "Net-(J1-Pad7)") (class "Default")
      (node (ref "J1") (pin "7") (pinfunction "7_7") (pintype "passive"))
      (node (ref "R17") (pin "1") (pintype "passive"))
      (node (ref "R19") (pin "2") (pintype "passive"))
    )
    (net (code "21") (name "Net-(J1-Pad8)") (class "Default")
      (node (ref "J1") (pin "8") (pinfunction "8_8") (pintype "passive"))
      (node (ref "R20") (pin "1") (pintype "passive"))
      (node (ref "R21") (pin "2") (pintype "passive"))
    )
    (net (code "22") (name "Net-(J1-Pad9)") (class "Default")
      (node (ref "J1") (pin "9") (pinfunction "9_9") (pintype "passive"))
      (node (ref "R22") (pin "1") (pintype "passive"))
      (node (ref "R23") (pin "2") (pintype "passive"))
    )
    (net (code "23") (name "Net-(J1-Pad10)") (class "Default")
      (node (ref "J1") (pin "10") (pinfunction "10_10") (pintype "passive"))
      (node (ref "R24") (pin "1") (pintype "passive"))
      (node (ref "R25") (pin "2") (pintype "passive"))
    )
    (net (code "24") (name "Net-(J1-Pad11)") (class "Default")
      (node (ref "J1") (pin "11") (pinfunction "11_11") (pintype "passive"))
      (node (ref "R26") (pin "1") (pintype "passive"))
      (node (ref "R27") (pin "2") (pintype "passive"))
    )
    (net (code "25") (name "Net-(J1-Pad12)") (class "Default")
      (node (ref "J1") (pin "12") (pinfunction "12_12") (pintype "passive"))
      (node (ref "R28") (pin "1") (pintype "passive"))
      (node (ref "R30") (pin "2") (pintype "passive"))
    )
    (net (code "26") (name "Net-(J1-Pad13)") (class "Default")
      (node (ref "J1") (pin "13") (pinfunction "13_13") (pintype "passive"))
      (node (ref "R32") (pin "1") (pintype "passive"))
      (node (ref "R33") (pin "2") (pintype "passive"))
    )
    (net (code "27") (name "Net-(J2-Pad2)") (class "Default")
      (node (ref "J2") (pin "2") (pinfunction "2_2") (pintype "passive"))
      (node (ref "J3") (pin "02") (pinfunction "02_02") (pintype "passive"))
    )
    (net (code "28") (name "Net-(J2-Pad4)") (class "Default")
      (node (ref "J2") (pin "4") (pinfunction "4_4") (pintype "passive"))
      (node (ref "J3") (pin "04") (pinfunction "04_04") (pintype "passive"))
    )
    (net (code "29") (name "Net-(J2-Pad5)") (class "Default")
      (node (ref "J2") (pin "5") (pinfunction "5_5") (pintype "passive"))
      (node (ref "J3") (pin "05") (pinfunction "05_05") (pintype "passive"))
    )
    (net (code "30") (name "Net-(J2-Pad6)") (class "Default")
      (node (ref "J2") (pin "6") (pinfunction "6_6") (pintype "passive"))
      (node (ref "J3") (pin "06") (pinfunction "06_06") (pintype "passive"))
    )
    (net (code "31") (name "Net-(U1B-PG3)") (class "Default")
      (node (ref "R18") (pin "2") (pintype "passive"))
      (node (ref "U1") (pin "88") (pinfunction "PG3_88") (pintype "passive"))
    )
    (net (code "32") (name "Net-(U1B-PG7)") (class "Default")
      (node (ref "R16") (pin "2") (pintype "passive"))
      (node (ref "U1") (pin "92") (pinfunction "PG7_92") (pintype "passive"))
    )
    (net (code "33") (name "SPI1_MISO") (class "Default")
      (node (ref "C18") (pin "2") (pinfunction "2_2") (pintype "passive"))
      (node (ref "R28") (pin "2") (pintype "passive"))
      (node (ref "U1") (pin "41") (pinfunction "PA6_41") (pintype "passive"))
    )
    (net (code "34") (name "SPI1_MOSI") (class "Default")
      (node (ref "C19") (pin "2") (pinfunction "2_2") (pintype "passive"))
      (node (ref "R32") (pin "2") (pintype "passive"))
      (node (ref "U1") (pin "75") (pinfunction "PB14_75") (pintype "passive"))
    )
    (net (code "35") (name "SPI1_SCLK") (class "Default")
      (node (ref "C17") (pin "2") (pinfunction "2_2") (pintype "passive"))
      (node (ref "R26") (pin "2") (pintype "passive"))
      (node (ref "U1") (pin "40") (pinfunction "PA5_40") (pintype "passive"))
      (node (ref "U1") (pin "74") (pinfunction "PB13_74") (pintype "passive"))
    )
    (net (code "36") (name "SWCLK") (class "Default")
      (node (ref "J4") (pin "02") (pinfunction "02_02") (pintype "passive"))
      (node (ref "U1") (pin "109") (pinfunction "*PA14_109") (pintype "passive"))
    )
    (net (code "37") (name "SWDIO") (class "Default")
      (node (ref "J4") (pin "04") (pinfunction "04_04") (pintype "passive"))
      (node (ref "U1") (pin "105") (pinfunction "PA13_105") (pintype "passive"))
    )
    (net (code "38") (name "SWO") (class "Default")
      (node (ref "J4") (pin "06") (pinfunction "06_06") (pintype "passive"))
      (node (ref "U1") (pin "132") (pinfunction "*PB3_132") (pintype "passive"))
    )
    (net (code "39") (name "UART1_OBC_RX") (class "Default")
      (node (ref "C1") (pin "2") (pinfunction "2_2") (pintype "passive"))
      (node (ref "R1") (pin "2") (pintype "passive"))
      (node (ref "U1") (pin "116") (pinfunction "*PD2_116") (pintype "passive"))
    )
    (net (code "40") (name "UART1_OBC_TX") (class "Default")
      (node (ref "C4") (pin "2") (pinfunction "2_2") (pintype "passive"))
      (node (ref "R3") (pin "2") (pintype "passive"))
      (node (ref "U1") (pin "26") (pinfunction "PC0_26") (pintype "open_collector"))
    )
    (net (code "41") (name "UART3_OBC_RX") (class "Default")
      (node (ref "C5") (pin "2") (pinfunction "2_2") (pintype "passive"))
      (node (ref "R5") (pin "2") (pintype "passive"))
      (node (ref "U1") (pin "34") (pinfunction "PA1_34") (pintype "open_collector"))
    )
    (net (code "42") (name "UART3_OBC_TX") (class "Default")
      (node (ref "C7") (pin "2") (pinfunction "2_2") (pintype "passive"))
      (node (ref "R7") (pin "2") (pintype "passive"))
      (node (ref "U1") (pin "36") (pinfunction "PA3_36") (pintype "open_collector"))
    )
    (net (code "43") (name "UART4_OBC_RX") (class "Default")
      (node (ref "C9") (pin "2") (pinfunction "2_2") (pintype "passive"))
      (node (ref "R9") (pin "2") (pintype "passive"))
      (node (ref "U1") (pin "67") (pinfunction "PB11_67") (pintype "passive"))
    )
    (net (code "44") (name "UART4_OBC_TX") (class "Default")
      (node (ref "C11") (pin "2") (pinfunction "2_2") (pintype "passive"))
      (node (ref "R12") (pin "2") (pintype "passive"))
      (node (ref "U1") (pin "102") (pinfunction "PA10_102") (pintype "passive"))
    )
    (net (code "45") (name "unconnected-(J5-ID-Pad4)") (class "Default")
      (node (ref "J5") (pin "4") (pinfunction "ID_4") (pintype "passive+no_connect"))
    )
    (net (code "46") (name "unconnected-(J5-SHIELD-PadS1)") (class "Default")
      (node (ref "J5") (pin "S1") (pinfunction "SHIELD_S1") (pintype "passive+no_connect"))
    )
    (net (code "47") (name "unconnected-(J5-SHIELD-PadS2)") (class "Default")
      (node (ref "J5") (pin "S2") (pinfunction "SHIELD_S2") (pintype "passive+no_connect"))
    )
    (net (code "48") (name "unconnected-(J5-SHIELD-PadS3)") (class "Default")
      (node (ref "J5") (pin "S3") (pinfunction "SHIELD_S3") (pintype "passive+no_connect"))
    )
    (net (code "49") (name "unconnected-(J5-SHIELD-PadS4)") (class "Default")
      (node (ref "J5") (pin "S4") (pinfunction "SHIELD_S4") (pintype "passive+no_connect"))
    )
    (net (code "50") (name "unconnected-(U1A-PA0-Pad33)") (class "Default")
      (node (ref "U1") (pin "33") (pinfunction "PA0_33") (pintype "open_collector+no_connect"))
    )
    (net (code "51") (name "unconnected-(U1A-PA2-Pad35)") (class "Default")
      (node (ref "U1") (pin "35") (pinfunction "PA2_35") (pintype "open_collector+no_connect"))
    )
    (net (code "52") (name "unconnected-(U1A-PA4-Pad39)") (class "Default")
      (node (ref "U1") (pin "39") (pinfunction "PA4_39") (pintype "passive+no_connect"))
    )
    (net (code "53") (name "unconnected-(U1A-PA7-Pad42)") (class "Default")
      (node (ref "U1") (pin "42") (pinfunction "PA7_42") (pintype "passive+no_connect"))
    )
    (net (code "54") (name "unconnected-(U1A-PB0-Pad43)") (class "Default")
      (node (ref "U1") (pin "43") (pinfunction "PB0_43") (pintype "passive"))
    )
    (net (code "55") (name "unconnected-(U1A-PB1-Pad44)") (class "Default")
      (node (ref "U1") (pin "44") (pinfunction "PB1_44") (pintype "passive+no_connect"))
    )
    (net (code "56") (name "unconnected-(U1A-PB2-Pad45)") (class "Default")
      (node (ref "U1") (pin "45") (pinfunction "PB2_45") (pintype "passive+no_connect"))
    )
    (net (code "57") (name "unconnected-(U1A-PB10-Pad66)") (class "Default")
      (node (ref "U1") (pin "66") (pinfunction "PB10_66") (pintype "passive+no_connect"))
    )
    (net (code "58") (name "unconnected-(U1A-PC1-Pad27)") (class "Default")
      (node (ref "U1") (pin "27") (pinfunction "PC1_27") (pintype "open_collector+no_connect"))
    )
    (net (code "59") (name "unconnected-(U1A-PC2-Pad28)") (class "Default")
      (node (ref "U1") (pin "28") (pinfunction "PC2_28") (pintype "open_collector+no_connect"))
    )
    (net (code "60") (name "unconnected-(U1A-PC3-Pad29)") (class "Default")
      (node (ref "U1") (pin "29") (pinfunction "PC3_29") (pintype "open_collector+no_connect"))
    )
    (net (code "61") (name "unconnected-(U1A-PC13-Pad7)") (class "Default")
      (node (ref "U1") (pin "7") (pinfunction "PC13_7") (pintype "passive+no_connect"))
    )
    (net (code "62") (name "unconnected-(U1A-PC14-OSC32_IN-Pad8)") (class "Default")
      (node (ref "U1") (pin "8") (pinfunction "PC14-OSC32_IN_8") (pintype "passive+no_connect"))
    )
    (net (code "63") (name "unconnected-(U1A-PC15-OSC32_OUT-Pad9)") (class "Default")
      (node (ref "U1") (pin "9") (pinfunction "PC15-OSC32_OUT_9") (pintype "passive+no_connect"))
    )
    (net (code "64") (name "unconnected-(U1A-PE2-Pad1)") (class "Default")
      (node (ref "U1") (pin "1") (pinfunction "PE2_1") (pintype "passive+no_connect"))
    )
    (net (code "65") (name "unconnected-(U1A-PE3-Pad2)") (class "Default")
      (node (ref "U1") (pin "2") (pinfunction "PE3_2") (pintype "passive+no_connect"))
    )
    (net (code "66") (name "unconnected-(U1A-PE4-Pad3)") (class "Default")
      (node (ref "U1") (pin "3") (pinfunction "PE4_3") (pintype "passive+no_connect"))
    )
    (net (code "67") (name "unconnected-(U1A-PE5-Pad4)") (class "Default")
      (node (ref "U1") (pin "4") (pinfunction "PE5_4") (pintype "passive+no_connect"))
    )
    (net (code "68") (name "unconnected-(U1A-PE6-Pad5)") (class "Default")
      (node (ref "U1") (pin "5") (pinfunction "PE6_5") (pintype "passive+no_connect"))
    )
    (net (code "69") (name "unconnected-(U1A-PE7-Pad55)") (class "Default")
      (node (ref "U1") (pin "55") (pinfunction "PE7_55") (pintype "passive+no_connect"))
    )
    (net (code "70") (name "unconnected-(U1A-PE8-Pad56)") (class "Default")
      (node (ref "U1") (pin "56") (pinfunction "PE8_56") (pintype "passive+no_connect"))
    )
    (net (code "71") (name "unconnected-(U1A-PE9-Pad57)") (class "Default")
      (node (ref "U1") (pin "57") (pinfunction "PE9_57") (pintype "passive+no_connect"))
    )
    (net (code "72") (name "unconnected-(U1A-PE10-Pad60)") (class "Default")
      (node (ref "U1") (pin "60") (pinfunction "PE10_60") (pintype "passive+no_connect"))
    )
    (net (code "73") (name "unconnected-(U1A-PE11-Pad61)") (class "Default")
      (node (ref "U1") (pin "61") (pinfunction "PE11_61") (pintype "passive+no_connect"))
    )
    (net (code "74") (name "unconnected-(U1A-PE12-Pad62)") (class "Default")
      (node (ref "U1") (pin "62") (pinfunction "PE12_62") (pintype "passive+no_connect"))
    )
    (net (code "75") (name "unconnected-(U1A-PE13-Pad63)") (class "Default")
      (node (ref "U1") (pin "63") (pinfunction "PE13_63") (pintype "passive+no_connect"))
    )
    (net (code "76") (name "unconnected-(U1A-PE14-Pad64)") (class "Default")
      (node (ref "U1") (pin "64") (pinfunction "PE14_64") (pintype "passive+no_connect"))
    )
    (net (code "77") (name "unconnected-(U1A-PE15-Pad65)") (class "Default")
      (node (ref "U1") (pin "65") (pinfunction "PE15_65") (pintype "passive+no_connect"))
    )
    (net (code "78") (name "unconnected-(U1A-PF0-Pad10)") (class "Default")
      (node (ref "U1") (pin "10") (pinfunction "PF0_10") (pintype "passive+no_connect"))
    )
    (net (code "79") (name "unconnected-(U1A-PF1-Pad11)") (class "Default")
      (node (ref "U1") (pin "11") (pinfunction "PF1_11") (pintype "passive+no_connect"))
    )
    (net (code "80") (name "unconnected-(U1A-PF2-Pad12)") (class "Default")
      (node (ref "U1") (pin "12") (pinfunction "PF2_12") (pintype "passive+no_connect"))
    )
    (net (code "81") (name "unconnected-(U1A-PF3-Pad13)") (class "Default")
      (node (ref "U1") (pin "13") (pinfunction "PF3_13") (pintype "passive+no_connect"))
    )
    (net (code "82") (name "unconnected-(U1A-PF4-Pad14)") (class "Default")
      (node (ref "U1") (pin "14") (pinfunction "PF4_14") (pintype "passive+no_connect"))
    )
    (net (code "83") (name "unconnected-(U1A-PF5-Pad15)") (class "Default")
      (node (ref "U1") (pin "15") (pinfunction "PF5_15") (pintype "passive+no_connect"))
    )
    (net (code "84") (name "unconnected-(U1A-PF6-Pad18)") (class "Default")
      (node (ref "U1") (pin "18") (pinfunction "PF6_18") (pintype "open_collector+no_connect"))
    )
    (net (code "85") (name "unconnected-(U1A-PF7-Pad19)") (class "Default")
      (node (ref "U1") (pin "19") (pinfunction "PF7_19") (pintype "open_collector+no_connect"))
    )
    (net (code "86") (name "unconnected-(U1A-PF8-Pad20)") (class "Default")
      (node (ref "U1") (pin "20") (pinfunction "PF8_20") (pintype "open_collector+no_connect"))
    )
    (net (code "87") (name "unconnected-(U1A-PF9-Pad21)") (class "Default")
      (node (ref "U1") (pin "21") (pinfunction "PF9_21") (pintype "open_collector+no_connect"))
    )
    (net (code "88") (name "unconnected-(U1A-PF10-Pad22)") (class "Default")
      (node (ref "U1") (pin "22") (pinfunction "PF10_22") (pintype "open_collector+no_connect"))
    )
    (net (code "89") (name "unconnected-(U1A-PF11-Pad46)") (class "Default")
      (node (ref "U1") (pin "46") (pinfunction "PF11_46") (pintype "passive+no_connect"))
    )
    (net (code "90") (name "unconnected-(U1A-PF12-Pad47)") (class "Default")
      (node (ref "U1") (pin "47") (pinfunction "PF12_47") (pintype "passive+no_connect"))
    )
    (net (code "91") (name "unconnected-(U1A-PF13-Pad50)") (class "Default")
      (node (ref "U1") (pin "50") (pinfunction "PF13_50") (pintype "passive+no_connect"))
    )
    (net (code "92") (name "unconnected-(U1A-PG0-Pad53)") (class "Default")
      (node (ref "U1") (pin "53") (pinfunction "PG0_53") (pintype "passive+no_connect"))
    )
    (net (code "93") (name "unconnected-(U1A-PG1-Pad54)") (class "Default")
      (node (ref "U1") (pin "54") (pinfunction "PG1_54") (pintype "passive+no_connect"))
    )
    (net (code "94") (name "unconnected-(U1A-PH1-OSC_OUT-Pad24)") (class "Default")
      (node (ref "U1") (pin "24") (pinfunction "PH1-OSC_OUT_24") (pintype "open_collector+no_connect"))
    )
    (net (code "95") (name "unconnected-(U1A-V15SMPS_1-Pad72)") (class "Default")
      (node (ref "U1") (pin "72") (pinfunction "V15SMPS_1_72") (pintype "power_in"))
    )
    (net (code "96") (name "unconnected-(U1A-VDDA-Pad32)") (class "Default")
      (node (ref "U1") (pin "32") (pinfunction "VDDA_32") (pintype "open_collector"))
    )
    (net (code "97") (name "unconnected-(U1A-VDDSMPS-Pad68)") (class "Default")
      (node (ref "U1") (pin "68") (pinfunction "VDDSMPS_68") (pintype "power_in"))
    )
    (net (code "98") (name "unconnected-(U1A-VLXSMPS-Pad69)") (class "Default")
      (node (ref "U1") (pin "69") (pinfunction "VLXSMPS_69") (pintype "power_in"))
    )
    (net (code "99") (name "unconnected-(U1A-VREF+-Pad31)") (class "Default")
      (node (ref "U1") (pin "31") (pinfunction "VREF+_31") (pintype "open_collector"))
    )
    (net (code "100") (name "unconnected-(U1A-VSSA{slash}VREF--Pad30)") (class "Default")
      (node (ref "U1") (pin "30") (pinfunction "VSSA/VREF-_30") (pintype "open_collector"))
    )
    (net (code "101") (name "unconnected-(U1A-VSSSMPS-Pad70)") (class "Default")
      (node (ref "U1") (pin "70") (pinfunction "VSSSMPS_70") (pintype "passive"))
    )
    (net (code "102") (name "unconnected-(U1B-*PA15-Pad110)") (class "Default")
      (node (ref "U1") (pin "110") (pinfunction "*PA15_110") (pintype "passive"))
    )
    (net (code "103") (name "unconnected-(U1B-*PB4-Pad133)") (class "Default")
      (node (ref "U1") (pin "133") (pinfunction "*PB4_133") (pintype "passive"))
    )
    (net (code "104") (name "unconnected-(U1B-*PB5-Pad134)") (class "Default")
      (node (ref "U1") (pin "134") (pinfunction "*PB5_134") (pintype "passive"))
    )
    (net (code "105") (name "unconnected-(U1B-*PB6-Pad135)") (class "Default")
      (node (ref "U1") (pin "135") (pinfunction "*PB6_135") (pintype "passive"))
    )
    (net (code "106") (name "unconnected-(U1B-*PB7-Pad136)") (class "Default")
      (node (ref "U1") (pin "136") (pinfunction "*PB7_136") (pintype "passive"))
    )
    (net (code "107") (name "unconnected-(U1B-*PB8-Pad138)") (class "Default")
      (node (ref "U1") (pin "138") (pinfunction "*PB8_138") (pintype "passive"))
    )
    (net (code "108") (name "unconnected-(U1B-*PB9-Pad139)") (class "Default")
      (node (ref "U1") (pin "139") (pinfunction "*PB9_139") (pintype "passive"))
    )
    (net (code "109") (name "unconnected-(U1B-*PC10-Pad111)") (class "Default")
      (node (ref "U1") (pin "111") (pinfunction "*PC10_111") (pintype "passive"))
    )
    (net (code "110") (name "unconnected-(U1B-*PC11-Pad112)") (class "Default")
      (node (ref "U1") (pin "112") (pinfunction "*PC11_112") (pintype "passive"))
    )
    (net (code "111") (name "unconnected-(U1B-*PC12-Pad113)") (class "Default")
      (node (ref "U1") (pin "113") (pinfunction "*PC12_113") (pintype "passive+no_connect"))
    )
    (net (code "112") (name "unconnected-(U1B-*PD0-Pad114)") (class "Default")
      (node (ref "U1") (pin "114") (pinfunction "*PD0_114") (pintype "passive"))
    )
    (net (code "113") (name "unconnected-(U1B-*PD1-Pad115)") (class "Default")
      (node (ref "U1") (pin "115") (pinfunction "*PD1_115") (pintype "passive"))
    )
    (net (code "114") (name "unconnected-(U1B-*PD3-Pad117)") (class "Default")
      (node (ref "U1") (pin "117") (pinfunction "*PD3_117") (pintype "passive"))
    )
    (net (code "115") (name "unconnected-(U1B-*PD4-Pad118)") (class "Default")
      (node (ref "U1") (pin "118") (pinfunction "*PD4_118") (pintype "passive"))
    )
    (net (code "116") (name "unconnected-(U1B-*PD5-Pad119)") (class "Default")
      (node (ref "U1") (pin "119") (pinfunction "*PD5_119") (pintype "passive"))
    )
    (net (code "117") (name "unconnected-(U1B-*PD6-Pad122)") (class "Default")
      (node (ref "U1") (pin "122") (pinfunction "*PD6_122") (pintype "passive"))
    )
    (net (code "118") (name "unconnected-(U1B-*PD7-Pad123)") (class "Default")
      (node (ref "U1") (pin "123") (pinfunction "*PD7_123") (pintype "passive"))
    )
    (net (code "119") (name "unconnected-(U1B-*PE0-Pad140)") (class "Default")
      (node (ref "U1") (pin "140") (pinfunction "*PE0_140") (pintype "passive"))
    )
    (net (code "120") (name "unconnected-(U1B-*PE1-Pad141)") (class "Default")
      (node (ref "U1") (pin "141") (pinfunction "*PE1_141") (pintype "passive"))
    )
    (net (code "121") (name "unconnected-(U1B-*PG9-Pad124)") (class "Default")
      (node (ref "U1") (pin "124") (pinfunction "*PG9_124") (pintype "passive"))
    )
    (net (code "122") (name "unconnected-(U1B-*PG10-Pad125)") (class "Default")
      (node (ref "U1") (pin "125") (pinfunction "*PG10_125") (pintype "passive"))
    )
    (net (code "123") (name "unconnected-(U1B-*PG12-Pad126)") (class "Default")
      (node (ref "U1") (pin "126") (pinfunction "*PG12_126") (pintype "passive"))
    )
    (net (code "124") (name "unconnected-(U1B-*PG15-Pad131)") (class "Default")
      (node (ref "U1") (pin "131") (pinfunction "*PG15_131") (pintype "passive"))
    )
    (net (code "125") (name "unconnected-(U1B-*V15SMPS_2-Pad143)") (class "Default")
      (node (ref "U1") (pin "143") (pinfunction "*V15SMPS_2_143") (pintype "passive"))
    )
    (net (code "126") (name "unconnected-(U1B-PA8-Pad100)") (class "Default")
      (node (ref "U1") (pin "100") (pinfunction "PA8_100") (pintype "passive+no_connect"))
    )
    (net (code "127") (name "unconnected-(U1B-PA9-Pad101)") (class "Default")
      (node (ref "U1") (pin "101") (pinfunction "PA9_101") (pintype "passive+no_connect"))
    )
    (net (code "128") (name "unconnected-(U1B-PB15-Pad76)") (class "Default")
      (node (ref "U1") (pin "76") (pinfunction "PB15_76") (pintype "passive+no_connect"))
    )
    (net (code "129") (name "unconnected-(U1B-PC6-Pad96)") (class "Default")
      (node (ref "U1") (pin "96") (pinfunction "PC6_96") (pintype "passive+no_connect"))
    )
    (net (code "130") (name "unconnected-(U1B-PC7-Pad97)") (class "Default")
      (node (ref "U1") (pin "97") (pinfunction "PC7_97") (pintype "passive+no_connect"))
    )
    (net (code "131") (name "unconnected-(U1B-PC8-Pad98)") (class "Default")
      (node (ref "U1") (pin "98") (pinfunction "PC8_98") (pintype "passive+no_connect"))
    )
    (net (code "132") (name "unconnected-(U1B-PC9-Pad99)") (class "Default")
      (node (ref "U1") (pin "99") (pinfunction "PC9_99") (pintype "passive+no_connect"))
    )
    (net (code "133") (name "unconnected-(U1B-PD8-Pad77)") (class "Default")
      (node (ref "U1") (pin "77") (pinfunction "PD8_77") (pintype "passive+no_connect"))
    )
    (net (code "134") (name "unconnected-(U1B-PD9-Pad78)") (class "Default")
      (node (ref "U1") (pin "78") (pinfunction "PD9_78") (pintype "passive+no_connect"))
    )
    (net (code "135") (name "unconnected-(U1B-PD10-Pad79)") (class "Default")
      (node (ref "U1") (pin "79") (pinfunction "PD10_79") (pintype "passive+no_connect"))
    )
    (net (code "136") (name "unconnected-(U1B-PD11-Pad80)") (class "Default")
      (node (ref "U1") (pin "80") (pinfunction "PD11_80") (pintype "passive+no_connect"))
    )
    (net (code "137") (name "unconnected-(U1B-PD12-Pad81)") (class "Default")
      (node (ref "U1") (pin "81") (pinfunction "PD12_81") (pintype "passive+no_connect"))
    )
    (net (code "138") (name "unconnected-(U1B-PD13-Pad82)") (class "Default")
      (node (ref "U1") (pin "82") (pinfunction "PD13_82") (pintype "passive+no_connect"))
    )
    (net (code "139") (name "unconnected-(U1B-PD14-Pad85)") (class "Default")
      (node (ref "U1") (pin "85") (pinfunction "PD14_85") (pintype "passive+no_connect"))
    )
    (net (code "140") (name "unconnected-(U1B-PD15-Pad86)") (class "Default")
      (node (ref "U1") (pin "86") (pinfunction "PD15_86") (pintype "passive+no_connect"))
    )
    (net (code "141") (name "unconnected-(U1B-PG2-Pad87)") (class "Default")
      (node (ref "U1") (pin "87") (pinfunction "PG2_87") (pintype "passive+no_connect"))
    )
    (net (code "142") (name "unconnected-(U1B-PG4-Pad89)") (class "Default")
      (node (ref "U1") (pin "89") (pinfunction "PG4_89") (pintype "passive"))
    )
    (net (code "143") (name "unconnected-(U1B-PG5-Pad90)") (class "Default")
      (node (ref "U1") (pin "90") (pinfunction "PG5_90") (pintype "passive+no_connect"))
    )
    (net (code "144") (name "unconnected-(U1B-PG6-Pad91)") (class "Default")
      (node (ref "U1") (pin "91") (pinfunction "PG6_91") (pintype "passive+no_connect"))
    )
    (net (code "145") (name "unconnected-(U1B-PG8-Pad93)") (class "Default")
      (node (ref "U1") (pin "93") (pinfunction "PG8_93") (pintype "passive"))
    )
    (net (code "146") (name "unconnected-(U1B-VDDUSB-Pad106)") (class "Default")
      (node (ref "U1") (pin "106") (pinfunction "VDDUSB_106") (pintype "passive"))
    )
  )
)
